# sensorHubRev4.net
KiCad netlist of a schematic drawn in EAGLE
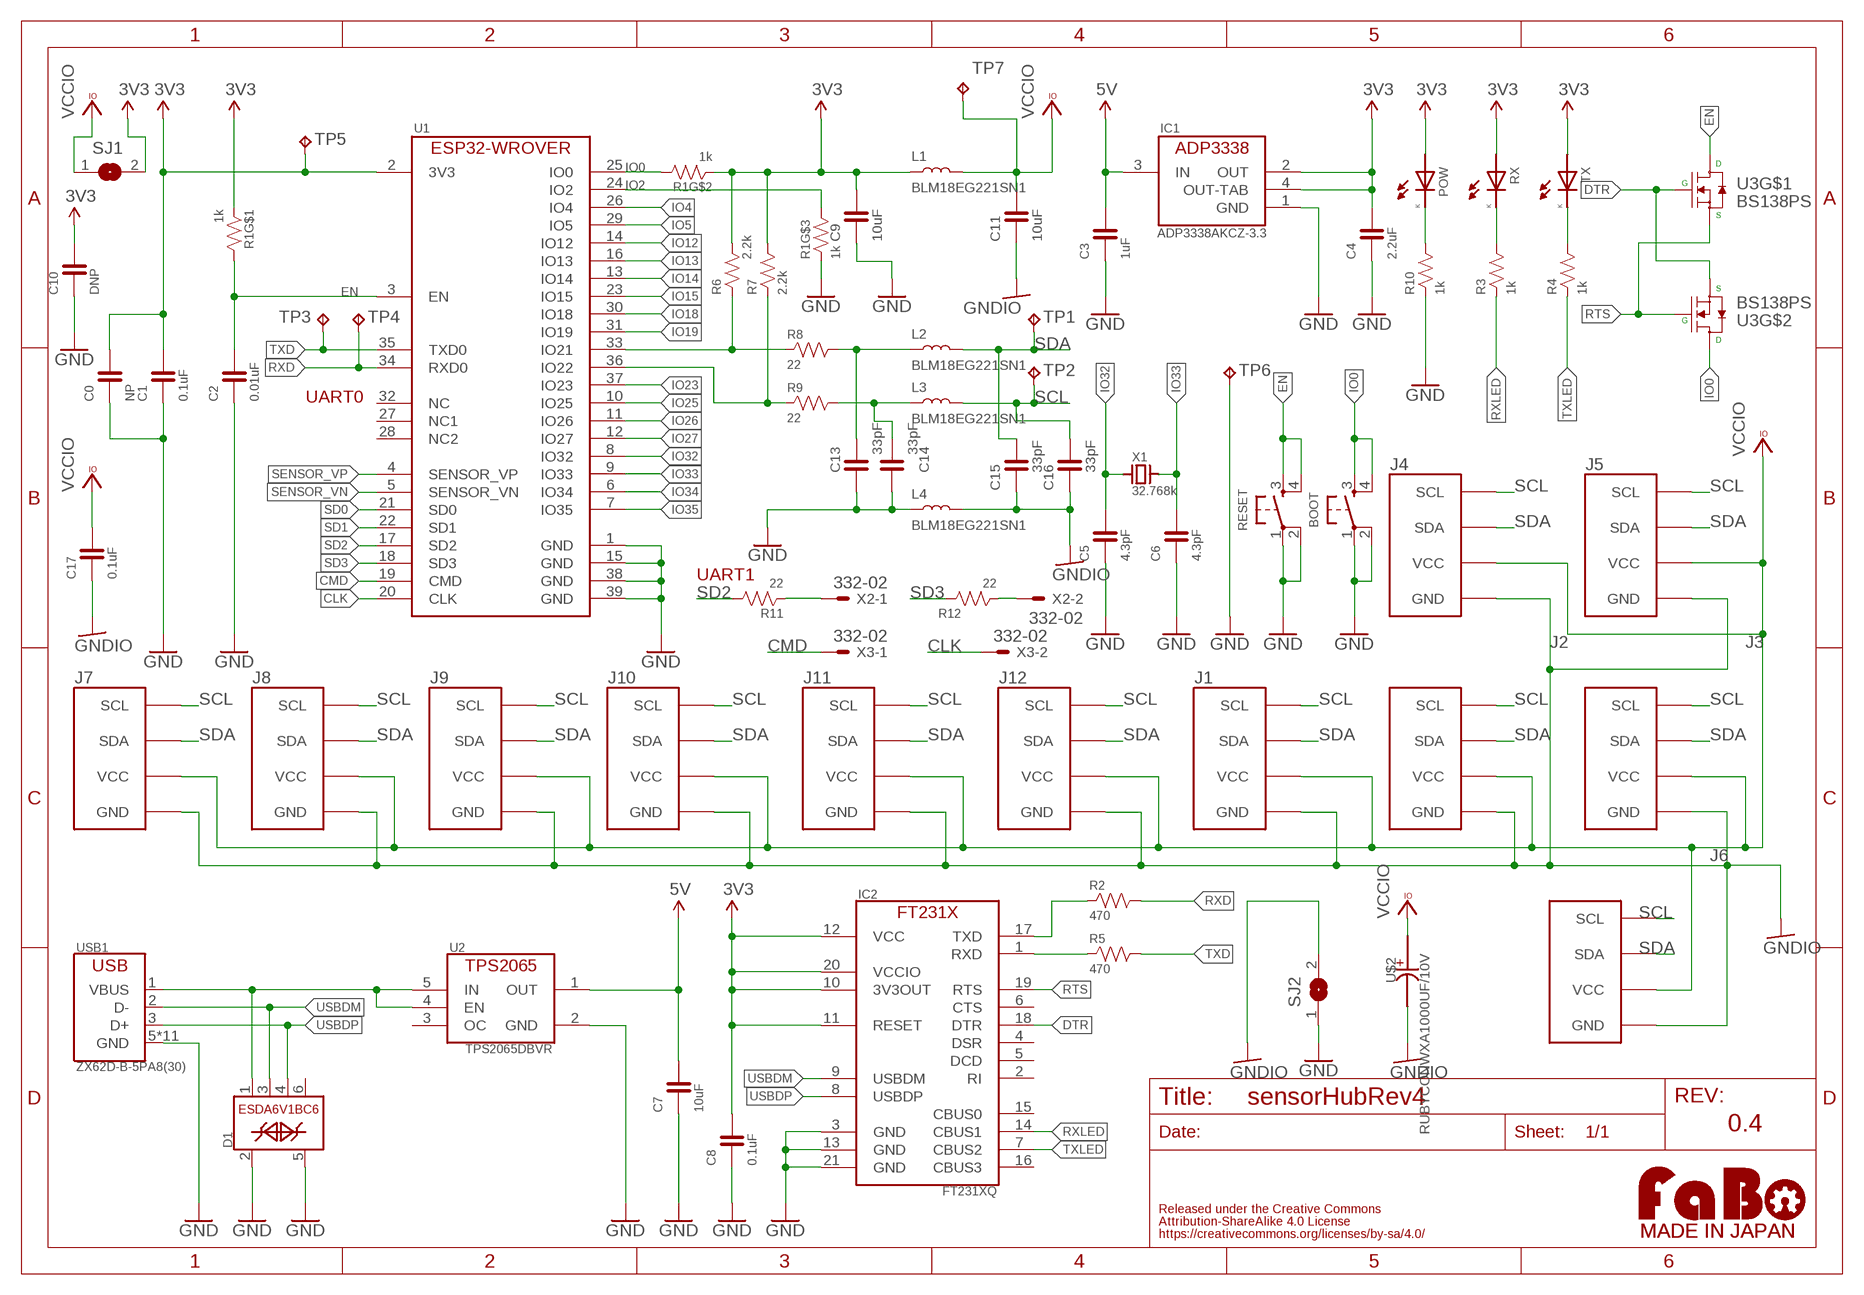
[diagram p0: schematic, sheet 1]

(export (version "E")
  (design (tool "Eeschema 10.0.6"))
  (components
    (comp (ref "BOOT")
      (value "TACTILE-KMR2")
      (footprint "eagle-import:KMR2-TACT")
      (libsource (lib "eagle-import") (part "TACTILE-KMR2"))
    )
    (comp (ref "C0")
      (value "NP")
      (footprint "eagle-import:MULTIPAD0603")
      (libsource (lib "eagle-import") (part "CAPACITOR-M"))
    )
    (comp (ref "C1")
      (value "0.1uF")
      (footprint "eagle-import:EIA0603")
      (libsource (lib "eagle-import") (part "component_CAPACITOR-0603"))
    )
    (comp (ref "C2")
      (value "0.01uF")
      (footprint "eagle-import:EIA0603")
      (libsource (lib "eagle-import") (part "component_CAPACITOR-0603"))
    )
    (comp (ref "C3")
      (value "1uF")
      (footprint "eagle-import:EIA0603")
      (libsource (lib "eagle-import") (part "component_CAPACITOR-0603"))
    )
    (comp (ref "C4")
      (value "2.2uF")
      (footprint "eagle-import:EIA0603")
      (libsource (lib "eagle-import") (part "component_CAPACITOR-0603"))
    )
    (comp (ref "C5")
      (value "4.3pF")
      (footprint "eagle-import:EIA0603")
      (libsource (lib "eagle-import") (part "component_CAPACITOR-0603"))
    )
    (comp (ref "C6")
      (value "4.3pF")
      (footprint "eagle-import:EIA0603")
      (libsource (lib "eagle-import") (part "component_CAPACITOR-0603"))
    )
    (comp (ref "C7")
      (value "10uF")
      (footprint "eagle-import:EIA0603")
      (libsource (lib "eagle-import") (part "component_CAPACITOR-0603"))
    )
    (comp (ref "C8")
      (value "0.1uF")
      (footprint "eagle-import:EIA0603")
      (libsource (lib "eagle-import") (part "component_CAPACITOR-0603"))
    )
    (comp (ref "C9")
      (value "10uF")
      (footprint "eagle-import:0603-NARROW")
      (libsource (lib "eagle-import") (part "CAPACITOR-0603_NARROW"))
    )
    (comp (ref "C10")
      (value "DNP")
      (footprint "eagle-import:EIA0603")
      (libsource (lib "eagle-import") (part "component_CAPACITOR-0603"))
    )
    (comp (ref "C11")
      (value "10uF")
      (footprint "eagle-import:0603-NARROW")
      (libsource (lib "eagle-import") (part "CAPACITOR-0603_NARROW"))
    )
    (comp (ref "C13")
      (value "33pF")
      (footprint "eagle-import:0603-NARROW")
      (libsource (lib "eagle-import") (part "CAPACITOR-0603_NARROW"))
    )
    (comp (ref "C14")
      (value "33pF")
      (footprint "eagle-import:0603-NARROW")
      (libsource (lib "eagle-import") (part "CAPACITOR-0603_NARROW"))
    )
    (comp (ref "C15")
      (value "33pF")
      (footprint "eagle-import:0603-NARROW")
      (libsource (lib "eagle-import") (part "CAPACITOR-0603_NARROW"))
    )
    (comp (ref "C16")
      (value "33pF")
      (footprint "eagle-import:0603-NARROW")
      (libsource (lib "eagle-import") (part "CAPACITOR-0603_NARROW"))
    )
    (comp (ref "C17")
      (value "0.1uF")
      (footprint "eagle-import:EIA0603")
      (libsource (lib "eagle-import") (part "component_CAPACITOR-0603"))
    )
    (comp (ref "D1")
      (value "ESDA6V1BC6")
      (footprint "eagle-import:SOT-23-6L")
      (libsource (lib "eagle-import") (part "ESDA6V1BC6"))
    )
    (comp (ref "IC1")
      (value "ADP3338AKCZ-3.3")
      (footprint "eagle-import:SOT-223-KC3")
      (libsource (lib "eagle-import") (part "ADP3338AKCZ"))
    )
    (comp (ref "IC2")
      (value "FT231XQ")
      (footprint "eagle-import:QFN-20")
      (libsource (lib "eagle-import") (part "FT231XQ"))
    )
    (comp (ref "J1")
      (value "FABO_BRICK_I2C-S04B-PASK-2")
      (footprint "eagle-import:FABO_BRICK_I2C_S04B-PASK-2")
      (libsource (lib "eagle-import") (part "FABO_BRICK_I2C-S04B-PASK-2"))
    )
    (comp (ref "J2")
      (value "FABO_BRICK_I2C-S04B-PASK-2")
      (footprint "eagle-import:FABO_BRICK_I2C_S04B-PASK-2")
      (libsource (lib "eagle-import") (part "FABO_BRICK_I2C-S04B-PASK-2"))
    )
    (comp (ref "J3")
      (value "FABO_BRICK_I2C-S04B-PASK-2")
      (footprint "eagle-import:FABO_BRICK_I2C_S04B-PASK-2")
      (libsource (lib "eagle-import") (part "FABO_BRICK_I2C-S04B-PASK-2"))
    )
    (comp (ref "J4")
      (value "FABO_BRICK_I2C-S04B-PASK-2")
      (footprint "eagle-import:FABO_BRICK_I2C_S04B-PASK-2")
      (libsource (lib "eagle-import") (part "FABO_BRICK_I2C-S04B-PASK-2"))
    )
    (comp (ref "J5")
      (value "FABO_BRICK_I2C-S04B-PASK-2")
      (footprint "eagle-import:FABO_BRICK_I2C_S04B-PASK-2")
      (libsource (lib "eagle-import") (part "FABO_BRICK_I2C-S04B-PASK-2"))
    )
    (comp (ref "J6")
      (value "FABO_BRICK_I2C-S04B-PASK-2")
      (footprint "eagle-import:FABO_BRICK_I2C_S04B-PASK-2")
      (libsource (lib "eagle-import") (part "FABO_BRICK_I2C-S04B-PASK-2"))
    )
    (comp (ref "J7")
      (value "FABO_BRICK_I2C-S04B-PASK-2")
      (footprint "eagle-import:FABO_BRICK_I2C_S04B-PASK-2")
      (libsource (lib "eagle-import") (part "FABO_BRICK_I2C-S04B-PASK-2"))
    )
    (comp (ref "J8")
      (value "FABO_BRICK_I2C-S04B-PASK-2")
      (footprint "eagle-import:FABO_BRICK_I2C_S04B-PASK-2")
      (libsource (lib "eagle-import") (part "FABO_BRICK_I2C-S04B-PASK-2"))
    )
    (comp (ref "J9")
      (value "FABO_BRICK_I2C-S04B-PASK-2")
      (footprint "eagle-import:FABO_BRICK_I2C_S04B-PASK-2")
      (libsource (lib "eagle-import") (part "FABO_BRICK_I2C-S04B-PASK-2"))
    )
    (comp (ref "J10")
      (value "FABO_BRICK_I2C-S04B-PASK-2")
      (footprint "eagle-import:FABO_BRICK_I2C_S04B-PASK-2")
      (libsource (lib "eagle-import") (part "FABO_BRICK_I2C-S04B-PASK-2"))
    )
    (comp (ref "J11")
      (value "FABO_BRICK_I2C-S04B-PASK-2")
      (footprint "eagle-import:FABO_BRICK_I2C_S04B-PASK-2")
      (libsource (lib "eagle-import") (part "FABO_BRICK_I2C-S04B-PASK-2"))
    )
    (comp (ref "J12")
      (value "FABO_BRICK_I2C-S04B-PASK-2")
      (footprint "eagle-import:FABO_BRICK_I2C_S04B-PASK-2")
      (libsource (lib "eagle-import") (part "FABO_BRICK_I2C-S04B-PASK-2"))
    )
    (comp (ref "L1")
      (value "BLM18EG221SN1")
      (footprint "eagle-import:0603")
      (libsource (lib "eagle-import") (part "INDUCTOR-0603"))
    )
    (comp (ref "L2")
      (value "BLM18EG221SN1")
      (footprint "eagle-import:0603")
      (libsource (lib "eagle-import") (part "INDUCTOR-0603"))
    )
    (comp (ref "L3")
      (value "BLM18EG221SN1")
      (footprint "eagle-import:0603")
      (libsource (lib "eagle-import") (part "INDUCTOR-0603"))
    )
    (comp (ref "L4")
      (value "BLM18EG221SN1")
      (footprint "eagle-import:0603")
      (libsource (lib "eagle-import") (part "INDUCTOR-0603"))
    )
    (comp (ref "LOGO1")
      (value "LOGO_FABO-M_BOTTOM")
      (footprint "eagle-import:LOGO_FABO_M_BOTTOM")
      (libsource (lib "eagle-import") (part "LOGO_FABO-M_BOTTOM"))
    )
    (comp (ref "POW")
      (value "LED-0603")
      (footprint "eagle-import:LED_0603")
      (libsource (lib "eagle-import") (part "LED-0603"))
    )
    (comp (ref "R1")
      (value "1k")
      (footprint "eagle-import:EXBV8V")
      (libsource (lib "eagle-import") (part "RESISTOR_ARRAY"))
    )
    (comp (ref "R2")
      (value "470")
      (footprint "eagle-import:EIA0603")
      (libsource (lib "eagle-import") (part "RESISTOR-0603"))
    )
    (comp (ref "R3")
      (value "1k")
      (footprint "eagle-import:EIA0603")
      (libsource (lib "eagle-import") (part "RESISTOR-0603"))
    )
    (comp (ref "R4")
      (value "1k")
      (footprint "eagle-import:EIA0603")
      (libsource (lib "eagle-import") (part "RESISTOR-0603"))
    )
    (comp (ref "R5")
      (value "470")
      (footprint "eagle-import:EIA0603")
      (libsource (lib "eagle-import") (part "RESISTOR-0603"))
    )
    (comp (ref "R6")
      (value "2.2k")
      (footprint "eagle-import:EIA0603")
      (libsource (lib "eagle-import") (part "RESISTOR-0603"))
    )
    (comp (ref "R7")
      (value "2.2k")
      (footprint "eagle-import:EIA0603")
      (libsource (lib "eagle-import") (part "RESISTOR-0603"))
    )
    (comp (ref "R8")
      (value "22")
      (footprint "eagle-import:EIA0603")
      (libsource (lib "eagle-import") (part "RESISTOR-0603"))
    )
    (comp (ref "R9")
      (value "22")
      (footprint "eagle-import:EIA0603")
      (libsource (lib "eagle-import") (part "RESISTOR-0603"))
    )
    (comp (ref "R10")
      (value "1k")
      (footprint "eagle-import:EIA0603")
      (libsource (lib "eagle-import") (part "RESISTOR-0603"))
    )
    (comp (ref "R11")
      (value "22")
      (footprint "eagle-import:EIA0603")
      (libsource (lib "eagle-import") (part "RESISTOR-0603"))
    )
    (comp (ref "R12")
      (value "22")
      (footprint "eagle-import:EIA0603")
      (libsource (lib "eagle-import") (part "RESISTOR-0603"))
    )
    (comp (ref "RESET")
      (value "TACTILE-KMR2")
      (footprint "eagle-import:KMR2-TACT")
      (libsource (lib "eagle-import") (part "TACTILE-KMR2"))
    )
    (comp (ref "RX")
      (value "LED-0603")
      (footprint "eagle-import:LED_0603")
      (libsource (lib "eagle-import") (part "LED-0603"))
    )
    (comp (ref "SJ1") (value "SJ") (footprint "eagle-import:SJ") (libsource (lib "eagle-import") (part "SJ")))
    (comp (ref "SJ2") (value "SJ") (footprint "eagle-import:SJ") (libsource (lib "eagle-import") (part "SJ")))
    (comp (ref "TP1")
      (value "TPB1,27")
      (footprint "eagle-import:B1,27")
      (libsource (lib "eagle-import") (part "TPB1,27"))
    )
    (comp (ref "TP2")
      (value "TPB1,27")
      (footprint "eagle-import:B1,27")
      (libsource (lib "eagle-import") (part "TPB1,27"))
    )
    (comp (ref "TP3")
      (value "TPB1,27")
      (footprint "eagle-import:B1,27")
      (libsource (lib "eagle-import") (part "TPB1,27"))
    )
    (comp (ref "TP4")
      (value "TPB1,27")
      (footprint "eagle-import:B1,27")
      (libsource (lib "eagle-import") (part "TPB1,27"))
    )
    (comp (ref "TP5")
      (value "TPB1,27")
      (footprint "eagle-import:B1,27")
      (libsource (lib "eagle-import") (part "TPB1,27"))
    )
    (comp (ref "TP6")
      (value "TPB1,27")
      (footprint "eagle-import:B1,27")
      (libsource (lib "eagle-import") (part "TPB1,27"))
    )
    (comp (ref "TP7")
      (value "TPB1,27")
      (footprint "eagle-import:B1,27")
      (libsource (lib "eagle-import") (part "TPB1,27"))
    )
    (comp (ref "TX")
      (value "LED-0603")
      (footprint "eagle-import:LED_0603")
      (libsource (lib "eagle-import") (part "LED-0603"))
    )
    (comp (ref "U$2")
      (value "RUBYCONWXA1000UF/10V")
      (footprint "eagle-import:ALUMINUM10_9")
      (libsource (lib "eagle-import") (part "RUBYCONWXA1000UF/10V"))
    )
    (comp (ref "U1")
      (value "ESP32-WROVER-B")
      (footprint "eagle-import:ESP32-WROVER-B")
      (libsource (lib "eagle-import") (part "ESP32-WROVER-B"))
    )
    (comp (ref "U2")
      (value "TPS2065DBVR")
      (footprint "eagle-import:SOT-23-5")
      (libsource (lib "eagle-import") (part "TPS2065DBV"))
    )
    (comp (ref "U3")
      (value "BS138PS")
      (footprint "eagle-import:SOT-363")
      (libsource (lib "eagle-import") (part "BS138PS"))
    )
    (comp (ref "USB1")
      (value "ZX62D-B-5PA8(30)")
      (footprint "eagle-import:ZX62D-B-5PA8")
      (libsource (lib "eagle-import") (part "USB-ZX62D"))
    )
    (comp (ref "X1")
      (value "32.768k")
      (footprint "eagle-import:ABS07")
      (libsource (lib "eagle-import") (part "CRYSTAL-ABS07"))
    )
    (comp (ref "X2")
      (value "332-02")
      (footprint "eagle-import:332-02")
      (libsource (lib "eagle-import") (part "332-02"))
    )
    (comp (ref "X3")
      (value "332-02")
      (footprint "eagle-import:332-02")
      (libsource (lib "eagle-import") (part "332-02"))
    )
  )
  (nets
    (net (code "1") (name "/IO2") (class "Default")
      (node (ref "R1") (pin "6") (pinfunction "2_6") (pintype "bidirectional"))
      (node (ref "U1") (pin "24") (pinfunction "IO2_24") (pintype "bidirectional"))
    )
    (net (code "2") (name "/SCL") (class "Default")
      (node (ref "C16") (pin "2") (pinfunction "2_2") (pintype "passive"))
      (node (ref "J1") (pin "SCL") (pinfunction "SCL_SCL") (pintype "bidirectional"))
      (node (ref "J10") (pin "SCL") (pinfunction "SCL_SCL") (pintype "bidirectional"))
      (node (ref "J11") (pin "SCL") (pinfunction "SCL_SCL") (pintype "bidirectional"))
      (node (ref "J12") (pin "SCL") (pinfunction "SCL_SCL") (pintype "bidirectional"))
      (node (ref "J2") (pin "SCL") (pinfunction "SCL_SCL") (pintype "bidirectional"))
      (node (ref "J3") (pin "SCL") (pinfunction "SCL_SCL") (pintype "bidirectional"))
      (node (ref "J4") (pin "SCL") (pinfunction "SCL_SCL") (pintype "bidirectional"))
      (node (ref "J5") (pin "SCL") (pinfunction "SCL_SCL") (pintype "bidirectional"))
      (node (ref "J6") (pin "SCL") (pinfunction "SCL_SCL") (pintype "bidirectional"))
      (node (ref "J7") (pin "SCL") (pinfunction "SCL_SCL") (pintype "bidirectional"))
      (node (ref "J8") (pin "SCL") (pinfunction "SCL_SCL") (pintype "bidirectional"))
      (node (ref "J9") (pin "SCL") (pinfunction "SCL_SCL") (pintype "bidirectional"))
      (node (ref "L3") (pin "2") (pinfunction "2_2") (pintype "bidirectional"))
      (node (ref "TP2") (pin "TP") (pinfunction "TP_TP") (pintype "input"))
    )
    (net (code "3") (name "/SDA") (class "Default")
      (node (ref "C15") (pin "2") (pinfunction "2_2") (pintype "passive"))
      (node (ref "J1") (pin "SDA") (pinfunction "SDA_SDA") (pintype "bidirectional"))
      (node (ref "J10") (pin "SDA") (pinfunction "SDA_SDA") (pintype "bidirectional"))
      (node (ref "J11") (pin "SDA") (pinfunction "SDA_SDA") (pintype "bidirectional"))
      (node (ref "J12") (pin "SDA") (pinfunction "SDA_SDA") (pintype "bidirectional"))
      (node (ref "J2") (pin "SDA") (pinfunction "SDA_SDA") (pintype "bidirectional"))
      (node (ref "J3") (pin "SDA") (pinfunction "SDA_SDA") (pintype "bidirectional"))
      (node (ref "J4") (pin "SDA") (pinfunction "SDA_SDA") (pintype "bidirectional"))
      (node (ref "J5") (pin "SDA") (pinfunction "SDA_SDA") (pintype "bidirectional"))
      (node (ref "J6") (pin "SDA") (pinfunction "SDA_SDA") (pintype "bidirectional"))
      (node (ref "J7") (pin "SDA") (pinfunction "SDA_SDA") (pintype "bidirectional"))
      (node (ref "J8") (pin "SDA") (pinfunction "SDA_SDA") (pintype "bidirectional"))
      (node (ref "J9") (pin "SDA") (pinfunction "SDA_SDA") (pintype "bidirectional"))
      (node (ref "L2") (pin "2") (pinfunction "2_2") (pintype "bidirectional"))
      (node (ref "TP1") (pin "TP") (pinfunction "TP_TP") (pintype "input"))
    )
    (net (code "4") (name "3V3") (class "Default")
      (node (ref "C0") (pin "2") (pinfunction "2_2") (pintype "passive"))
      (node (ref "C1") (pin "2") (pinfunction "2_2") (pintype "passive"))
      (node (ref "C10") (pin "2") (pinfunction "2_2") (pintype "passive"))
      (node (ref "C4") (pin "2") (pinfunction "2_2") (pintype "passive"))
      (node (ref "C8") (pin "2") (pinfunction "2_2") (pintype "passive"))
      (node (ref "C9") (pin "2") (pinfunction "2_2") (pintype "passive"))
      (node (ref "IC1") (pin "2") (pinfunction "OUT_2") (pintype "bidirectional"))
      (node (ref "IC1") (pin "4") (pinfunction "OUT-TAB_4") (pintype "bidirectional"))
      (node (ref "IC2") (pin "10") (pinfunction "3V3OUT_10") (pintype "bidirectional"))
      (node (ref "IC2") (pin "11") (pinfunction "RESET_11") (pintype "bidirectional"))
      (node (ref "IC2") (pin "12") (pinfunction "VCC_12") (pintype "bidirectional"))
      (node (ref "IC2") (pin "20") (pinfunction "VCCIO_20") (pintype "bidirectional"))
      (node (ref "L1") (pin "1") (pinfunction "1_1") (pintype "bidirectional"))
      (node (ref "POW") (pin "A") (pinfunction "ANODE_A") (pintype "passive"))
      (node (ref "R1") (pin "1") (pinfunction "1_1") (pintype "bidirectional"))
      (node (ref "R1") (pin "2") (pinfunction "1_2") (pintype "bidirectional"))
      (node (ref "R6") (pin "2") (pinfunction "2_2") (pintype "bidirectional"))
      (node (ref "R7") (pin "2") (pinfunction "2_2") (pintype "bidirectional"))
      (node (ref "RX") (pin "A") (pinfunction "ANODE_A") (pintype "passive"))
      (node (ref "SJ1") (pin "2") (pinfunction "2_2") (pintype "passive"))
      (node (ref "TP5") (pin "TP") (pinfunction "TP_TP") (pintype "input"))
      (node (ref "TX") (pin "A") (pinfunction "ANODE_A") (pintype "passive"))
      (node (ref "U1") (pin "2") (pinfunction "3V3_2") (pintype "bidirectional"))
    )
    (net (code "5") (name "5V") (class "Default")
      (node (ref "C3") (pin "2") (pinfunction "2_2") (pintype "passive"))
      (node (ref "C7") (pin "2") (pinfunction "2_2") (pintype "passive"))
      (node (ref "IC1") (pin "3") (pinfunction "IN_3") (pintype "bidirectional"))
      (node (ref "U2") (pin "1") (pinfunction "OUT_1") (pintype "bidirectional"))
    )
    (net (code "6") (name "CLK") (class "Default")
      (node (ref "U1") (pin "20") (pinfunction "CLK_20") (pintype "bidirectional"))
      (node (ref "X3") (pin "2") (pinfunction "S_2") (pintype "passive"))
    )
    (net (code "7") (name "CMD") (class "Default")
      (node (ref "U1") (pin "19") (pinfunction "CMD_19") (pintype "bidirectional"))
      (node (ref "X3") (pin "1") (pinfunction "S_1") (pintype "passive"))
    )
    (net (code "8") (name "DTR") (class "Default")
      (node (ref "IC2") (pin "18") (pinfunction "DTR_18") (pintype "bidirectional"))
      (node (ref "U3") (pin "2") (pinfunction "G_2") (pintype "passive"))
      (node (ref "U3") (pin "4") (pinfunction "S_4") (pintype "passive"))
    )
    (net (code "9") (name "EN") (class "Default")
      (node (ref "C2") (pin "2") (pinfunction "2_2") (pintype "passive"))
      (node (ref "R1") (pin "8") (pinfunction "2_8") (pintype "bidirectional"))
      (node (ref "RESET") (pin "3") (pinfunction "3_3") (pintype "passive"))
      (node (ref "RESET") (pin "4") (pinfunction "4_4") (pintype "passive"))
      (node (ref "U1") (pin "3") (pinfunction "EN_3") (pintype "bidirectional"))
      (node (ref "U3") (pin "6") (pinfunction "D_6") (pintype "passive"))
    )
    (net (code "10") (name "GND") (class "Default")
      (node (ref "BOOT") (pin "1") (pinfunction "1_1") (pintype "passive"))
      (node (ref "BOOT") (pin "2") (pinfunction "2_2") (pintype "passive"))
      (node (ref "C0") (pin "1") (pinfunction "1_1") (pintype "passive"))
      (node (ref "C1") (pin "1") (pinfunction "1_1") (pintype "passive"))
      (node (ref "C10") (pin "1") (pinfunction "1_1") (pintype "passive"))
      (node (ref "C13") (pin "1") (pinfunction "1_1") (pintype "passive"))
      (node (ref "C14") (pin "1") (pinfunction "1_1") (pintype "passive"))
      (node (ref "C2") (pin "1") (pinfunction "1_1") (pintype "passive"))
      (node (ref "C3") (pin "1") (pinfunction "1_1") (pintype "passive"))
      (node (ref "C4") (pin "1") (pinfunction "1_1") (pintype "passive"))
      (node (ref "C5") (pin "1") (pinfunction "1_1") (pintype "passive"))
      (node (ref "C6") (pin "1") (pinfunction "1_1") (pintype "passive"))
      (node (ref "C7") (pin "1") (pinfunction "1_1") (pintype "passive"))
      (node (ref "C8") (pin "1") (pinfunction "1_1") (pintype "passive"))
      (node (ref "C9") (pin "1") (pinfunction "1_1") (pintype "passive"))
      (node (ref "D1") (pin "2") (pinfunction "2_2") (pintype "bidirectional"))
      (node (ref "D1") (pin "5") (pinfunction "5_5") (pintype "bidirectional"))
      (node (ref "IC1") (pin "1") (pinfunction "GND_1") (pintype "bidirectional"))
      (node (ref "IC2") (pin "13") (pinfunction "GND_13") (pintype "bidirectional"))
      (node (ref "IC2") (pin "21") (pinfunction "GND_21") (pintype "bidirectional"))
      (node (ref "IC2") (pin "3") (pinfunction "GND_3") (pintype "bidirectional"))
      (node (ref "L4") (pin "1") (pinfunction "1_1") (pintype "bidirectional"))
      (node (ref "R1") (pin "3") (pinfunction "1_3") (pintype "bidirectional"))
      (node (ref "R10") (pin "1") (pinfunction "1_1") (pintype "bidirectional"))
      (node (ref "RESET") (pin "1") (pinfunction "1_1") (pintype "passive"))
      (node (ref "RESET") (pin "2") (pinfunction "2_2") (pintype "passive"))
      (node (ref "SJ2") (pin "1") (pinfunction "1_1") (pintype "passive"))
      (node (ref "TP6") (pin "TP") (pinfunction "TP_TP") (pintype "input"))
      (node (ref "U1") (pin "1") (pinfunction "GND_1") (pintype "bidirectional"))
      (node (ref "U1") (pin "15") (pinfunction "GND_15") (pintype "bidirectional"))
      (node (ref "U1") (pin "38") (pinfunction "GND_38") (pintype "bidirectional"))
      (node (ref "U1") (pin "39") (pinfunction "GND_39") (pintype "bidirectional"))
      (node (ref "U2") (pin "2") (pinfunction "GND_2") (pintype "bidirectional"))
      (node (ref "USB1") (pin "5") (pinfunction "GND_5") (pintype "bidirectional"))
      (node (ref "USB1") (pin "B1") (pinfunction "GND_B1") (pintype "bidirectional"))
      (node (ref "USB1") (pin "B2") (pinfunction "GND_B2") (pintype "bidirectional"))
      (node (ref "USB1") (pin "B3") (pinfunction "GND_B3") (pintype "bidirectional"))
      (node (ref "USB1") (pin "B4") (pinfunction "GND_B4") (pintype "bidirectional"))
      (node (ref "USB1") (pin "T1") (pinfunction "GND_T1") (pintype "bidirectional"))
      (node (ref "USB1") (pin "T2") (pinfunction "GND_T2") (pintype "bidirectional"))
      (node (ref "USB1") (pin "T3") (pinfunction "GND_T3") (pintype "bidirectional"))
      (node (ref "USB1") (pin "T4") (pinfunction "GND_T4") (pintype "bidirectional"))
      (node (ref "USB1") (pin "T5") (pinfunction "GND_T5") (pintype "bidirectional"))
      (node (ref "USB1") (pin "T6") (pinfunction "GND_T6") (pintype "bidirectional"))
    )
    (net (code "11") (name "GNDIO") (class "Default")
      (node (ref "C11") (pin "1") (pinfunction "1_1") (pintype "passive"))
      (node (ref "C15") (pin "1") (pinfunction "1_1") (pintype "passive"))
      (node (ref "C16") (pin "1") (pinfunction "1_1") (pintype "passive"))
      (node (ref "C17") (pin "1") (pinfunction "1_1") (pintype "passive"))
      (node (ref "J1") (pin "GND") (pinfunction "GND_GND") (pintype "bidirectional"))
      (node (ref "J10") (pin "GND") (pinfunction "GND_GND") (pintype "bidirectional"))
      (node (ref "J11") (pin "GND") (pinfunction "GND_GND") (pintype "bidirectional"))
      (node (ref "J12") (pin "GND") (pinfunction "GND_GND") (pintype "bidirectional"))
      (node (ref "J2") (pin "GND") (pinfunction "GND_GND") (pintype "bidirectional"))
      (node (ref "J3") (pin "GND") (pinfunction "GND_GND") (pintype "bidirectional"))
      (node (ref "J4") (pin "GND") (pinfunction "GND_GND") (pintype "bidirectional"))
      (node (ref "J5") (pin "GND") (pinfunction "GND_GND") (pintype "bidirectional"))
      (node (ref "J6") (pin "GND") (pinfunction "GND_GND") (pintype "bidirectional"))
      (node (ref "J7") (pin "GND") (pinfunction "GND_GND") (pintype "bidirectional"))
      (node (ref "J8") (pin "GND") (pinfunction "GND_GND") (pintype "bidirectional"))
      (node (ref "J9") (pin "GND") (pinfunction "GND_GND") (pintype "bidirectional"))
      (node (ref "L4") (pin "2") (pinfunction "2_2") (pintype "bidirectional"))
      (node (ref "SJ2") (pin "2") (pinfunction "2_2") (pintype "passive"))
      (node (ref "U$2") (pin "MINUS") (pinfunction "-_MINUS") (pintype "passive"))
    )
    (net (code "12") (name "IO0") (class "Default")
      (node (ref "BOOT") (pin "3") (pinfunction "3_3") (pintype "passive"))
      (node (ref "BOOT") (pin "4") (pinfunction "4_4") (pintype "passive"))
      (node (ref "R1") (pin "7") (pinfunction "2_7") (pintype "bidirectional"))
      (node (ref "U1") (pin "25") (pinfunction "IO0_25") (pintype "bidirectional"))
      (node (ref "U3") (pin "3") (pinfunction "D_3") (pintype "passive"))
    )
    (net (code "13") (name "IO4") (class "Default")
      (node (ref "U1") (pin "26") (pinfunction "IO4_26") (pintype "bidirectional"))
    )
    (net (code "14") (name "IO5") (class "Default")
      (node (ref "U1") (pin "29") (pinfunction "IO5_29") (pintype "bidirectional"))
    )
    (net (code "15") (name "IO12") (class "Default")
      (node (ref "U1") (pin "14") (pinfunction "IO12_14") (pintype "bidirectional"))
    )
    (net (code "16") (name "IO13") (class "Default")
      (node (ref "U1") (pin "16") (pinfunction "IO13_16") (pintype "bidirectional"))
    )
    (net (code "17") (name "IO14") (class "Default")
      (node (ref "U1") (pin "13") (pinfunction "IO14_13") (pintype "bidirectional"))
    )
    (net (code "18") (name "IO15") (class "Default")
      (node (ref "U1") (pin "23") (pinfunction "IO15_23") (pintype "bidirectional"))
    )
    (net (code "19") (name "IO18") (class "Default")
      (node (ref "U1") (pin "30") (pinfunction "IO18_30") (pintype "bidirectional"))
    )
    (net (code "20") (name "IO19") (class "Default")
      (node (ref "U1") (pin "31") (pinfunction "IO19_31") (pintype "bidirectional"))
    )
    (net (code "21") (name "IO23") (class "Default")
      (node (ref "U1") (pin "37") (pinfunction "IO23_37") (pintype "bidirectional"))
    )
    (net (code "22") (name "IO25") (class "Default")
      (node (ref "U1") (pin "10") (pinfunction "IO25_10") (pintype "bidirectional"))
    )
    (net (code "23") (name "IO26") (class "Default")
      (node (ref "U1") (pin "11") (pinfunction "IO26_11") (pintype "bidirectional"))
    )
    (net (code "24") (name "IO27") (class "Default")
      (node (ref "U1") (pin "12") (pinfunction "IO27_12") (pintype "bidirectional"))
    )
    (net (code "25") (name "IO32") (class "Default")
      (node (ref "C5") (pin "2") (pinfunction "2_2") (pintype "passive"))
      (node (ref "U1") (pin "8") (pinfunction "IO32_8") (pintype "bidirectional"))
      (node (ref "X1") (pin "1") (pinfunction "P$1_1") (pintype "bidirectional"))
    )
    (net (code "26") (name "IO33") (class "Default")
      (node (ref "C6") (pin "2") (pinfunction "2_2") (pintype "passive"))
      (node (ref "U1") (pin "9") (pinfunction "IO33_9") (pintype "bidirectional"))
      (node (ref "X1") (pin "2") (pinfunction "P$2_2") (pintype "bidirectional"))
    )
    (net (code "27") (name "IO34") (class "Default")
      (node (ref "U1") (pin "6") (pinfunction "IO34_6") (pintype "bidirectional"))
    )
    (net (code "28") (name "IO35") (class "Default")
      (node (ref "U1") (pin "7") (pinfunction "IO35_7") (pintype "bidirectional"))
    )
    (net (code "29") (name "Net-(C13-Pad2)") (class "Default")
      (node (ref "C13") (pin "2") (pinfunction "2_2") (pintype "passive"))
      (node (ref "L2") (pin "1") (pinfunction "1_1") (pintype "bidirectional"))
      (node (ref "R8") (pin "2") (pinfunction "2_2") (pintype "bidirectional"))
    )
    (net (code "30") (name "Net-(C14-Pad2)") (class "Default")
      (node (ref "C14") (pin "2") (pinfunction "2_2") (pintype "passive"))
      (node (ref "L3") (pin "1") (pinfunction "1_1") (pintype "bidirectional"))
      (node (ref "R9") (pin "2") (pinfunction "2_2") (pintype "bidirectional"))
    )
    (net (code "31") (name "Net-(IC2-RXD)") (class "Default")
      (node (ref "IC2") (pin "1") (pinfunction "RXD_1") (pintype "bidirectional"))
      (node (ref "R5") (pin "1") (pinfunction "1_1") (pintype "bidirectional"))
    )
    (net (code "32") (name "Net-(IC2-TXD)") (class "Default")
      (node (ref "IC2") (pin "17") (pinfunction "TXD_17") (pintype "bidirectional"))
      (node (ref "R2") (pin "1") (pinfunction "1_1") (pintype "bidirectional"))
    )
    (net (code "33") (name "Net-(POW-CATHODE)") (class "Default")
      (node (ref "POW") (pin "K") (pinfunction "CATHODE_K") (pintype "passive"))
      (node (ref "R10") (pin "2") (pinfunction "2_2") (pintype "bidirectional"))
    )
    (net (code "34") (name "Net-(RX-CATHODE)") (class "Default")
      (node (ref "R3") (pin "2") (pinfunction "2_2") (pintype "bidirectional"))
      (node (ref "RX") (pin "K") (pinfunction "CATHODE_K") (pintype "passive"))
    )
    (net (code "35") (name "Net-(TX-CATHODE)") (class "Default")
      (node (ref "R4") (pin "2") (pinfunction "2_2") (pintype "bidirectional"))
      (node (ref "TX") (pin "K") (pinfunction "CATHODE_K") (pintype "passive"))
    )
    (net (code "36") (name "Net-(U1-IO21)") (class "Default")
      (node (ref "R6") (pin "1") (pinfunction "1_1") (pintype "bidirectional"))
      (node (ref "R8") (pin "1") (pinfunction "1_1") (pintype "bidirectional"))
      (node (ref "U1") (pin "33") (pinfunction "IO21_33") (pintype "bidirectional"))
    )
    (net (code "37") (name "Net-(U1-IO22)") (class "Default")
      (node (ref "R7") (pin "1") (pinfunction "1_1") (pintype "bidirectional"))
      (node (ref "R9") (pin "1") (pinfunction "1_1") (pintype "bidirectional"))
      (node (ref "U1") (pin "36") (pinfunction "IO22_36") (pintype "bidirectional"))
    )
    (net (code "38") (name "Net-(U2-EN)") (class "Default")
      (node (ref "D1") (pin "1") (pinfunction "1_1") (pintype "bidirectional"))
      (node (ref "U2") (pin "4") (pinfunction "EN_4") (pintype "bidirectional"))
      (node (ref "U2") (pin "5") (pinfunction "IN_5") (pintype "bidirectional"))
      (node (ref "USB1") (pin "1") (pinfunction "VBUS_1") (pintype "bidirectional"))
    )
    (net (code "39") (name "Net-(X2A-S)") (class "Default")
      (node (ref "R11") (pin "1") (pinfunction "1_1") (pintype "bidirectional"))
      (node (ref "X2") (pin "1") (pinfunction "S_1") (pintype "passive"))
    )
    (net (code "40") (name "Net-(X2B-S)") (class "Default")
      (node (ref "R12") (pin "1") (pinfunction "1_1") (pintype "bidirectional"))
      (node (ref "X2") (pin "2") (pinfunction "S_2") (pintype "passive"))
    )
    (net (code "41") (name "RTS") (class "Default")
      (node (ref "IC2") (pin "19") (pinfunction "RTS_19") (pintype "bidirectional"))
      (node (ref "U3") (pin "1") (pinfunction "S_1") (pintype "passive"))
      (node (ref "U3") (pin "5") (pinfunction "G_5") (pintype "passive"))
    )
    (net (code "42") (name "RXD") (class "Default")
      (node (ref "R2") (pin "2") (pinfunction "2_2") (pintype "bidirectional"))
      (node (ref "TP4") (pin "TP") (pinfunction "TP_TP") (pintype "input"))
      (node (ref "U1") (pin "34") (pinfunction "RXD0_34") (pintype "bidirectional"))
    )
    (net (code "43") (name "RXLED") (class "Default")
      (node (ref "IC2") (pin "14") (pinfunction "CBUS1_14") (pintype "bidirectional"))
      (node (ref "R3") (pin "1") (pinfunction "1_1") (pintype "bidirectional"))
    )
    (net (code "44") (name "SD0") (class "Default")
      (node (ref "U1") (pin "21") (pinfunction "SD0_21") (pintype "bidirectional"))
    )
    (net (code "45") (name "SD1") (class "Default")
      (node (ref "U1") (pin "22") (pinfunction "SD1_22") (pintype "bidirectional"))
    )
    (net (code "46") (name "SD2") (class "Default")
      (node (ref "R11") (pin "2") (pinfunction "2_2") (pintype "bidirectional"))
      (node (ref "U1") (pin "17") (pinfunction "SD2_17") (pintype "bidirectional"))
    )
    (net (code "47") (name "SD3") (class "Default")
      (node (ref "R12") (pin "2") (pinfunction "2_2") (pintype "bidirectional"))
      (node (ref "U1") (pin "18") (pinfunction "SD3_18") (pintype "bidirectional"))
    )
    (net (code "48") (name "SENSOR_VN") (class "Default")
      (node (ref "U1") (pin "5") (pinfunction "SENSOR_VN_5") (pintype "bidirectional"))
    )
    (net (code "49") (name "SENSOR_VP") (class "Default")
      (node (ref "U1") (pin "4") (pinfunction "SENSOR_VP_4") (pintype "bidirectional"))
    )
    (net (code "50") (name "TXD") (class "Default")
      (node (ref "R5") (pin "2") (pinfunction "2_2") (pintype "bidirectional"))
      (node (ref "TP3") (pin "TP") (pinfunction "TP_TP") (pintype "input"))
      (node (ref "U1") (pin "35") (pinfunction "TXD0_35") (pintype "bidirectional"))
    )
    (net (code "51") (name "TXLED") (class "Default")
      (node (ref "IC2") (pin "7") (pinfunction "CBUS2_7") (pintype "bidirectional"))
      (node (ref "R4") (pin "1") (pinfunction "1_1") (pintype "bidirectional"))
    )
    (net (code "52") (name "USBDM") (class "Default")
      (node (ref "D1") (pin "3") (pinfunction "3_3") (pintype "bidirectional"))
      (node (ref "IC2") (pin "9") (pinfunction "USBDM_9") (pintype "bidirectional"))
      (node (ref "USB1") (pin "2") (pinfunction "D-_2") (pintype "bidirectional"))
    )
    (net (code "53") (name "USBDP") (class "Default")
      (node (ref "D1") (pin "4") (pinfunction "4_4") (pintype "bidirectional"))
      (node (ref "IC2") (pin "8") (pinfunction "USBDP_8") (pintype "bidirectional"))
      (node (ref "USB1") (pin "3") (pinfunction "D+_3") (pintype "bidirectional"))
    )
    (net (code "54") (name "VCCIO") (class "Default")
      (node (ref "C11") (pin "2") (pinfunction "2_2") (pintype "passive"))
      (node (ref "C17") (pin "2") (pinfunction "2_2") (pintype "passive"))
      (node (ref "J1") (pin "VCC") (pinfunction "VCC_VCC") (pintype "bidirectional"))
      (node (ref "J10") (pin "VCC") (pinfunction "VCC_VCC") (pintype "bidirectional"))
      (node (ref "J11") (pin "VCC") (pinfunction "VCC_VCC") (pintype "bidirectional"))
      (node (ref "J12") (pin "VCC") (pinfunction "VCC_VCC") (pintype "bidirectional"))
      (node (ref "J2") (pin "VCC") (pinfunction "VCC_VCC") (pintype "bidirectional"))
      (node (ref "J3") (pin "VCC") (pinfunction "VCC_VCC") (pintype "bidirectional"))
      (node (ref "J4") (pin "VCC") (pinfunction "VCC_VCC") (pintype "bidirectional"))
      (node (ref "J5") (pin "VCC") (pinfunction "VCC_VCC") (pintype "bidirectional"))
      (node (ref "J6") (pin "VCC") (pinfunction "VCC_VCC") (pintype "bidirectional"))
      (node (ref "J7") (pin "VCC") (pinfunction "VCC_VCC") (pintype "bidirectional"))
      (node (ref "J8") (pin "VCC") (pinfunction "VCC_VCC") (pintype "bidirectional"))
      (node (ref "J9") (pin "VCC") (pinfunction "VCC_VCC") (pintype "bidirectional"))
      (node (ref "L1") (pin "2") (pinfunction "2_2") (pintype "bidirectional"))
      (node (ref "SJ1") (pin "1") (pinfunction "1_1") (pintype "passive"))
      (node (ref "TP7") (pin "TP") (pinfunction "TP_TP") (pintype "input"))
      (node (ref "U$2") (pin "PLUS") (pinfunction "+_PLUS") (pintype "passive"))
    )
    (net (code "55") (name "unconnected-(D1-Pad6)") (class "Default")
      (node (ref "D1") (pin "6") (pinfunction "6_6") (pintype "bidirectional"))
    )
    (net (code "56") (name "unconnected-(IC2-CBUS0-Pad15)") (class "Default")
      (node (ref "IC2") (pin "15") (pinfunction "CBUS0_15") (pintype "bidirectional"))
    )
    (net (code "57") (name "unconnected-(IC2-CBUS3-Pad16)") (class "Default")
      (node (ref "IC2") (pin "16") (pinfunction "CBUS3_16") (pintype "bidirectional"))
    )
    (net (code "58") (name "unconnected-(IC2-CTS-Pad6)") (class "Default")
      (node (ref "IC2") (pin "6") (pinfunction "CTS_6") (pintype "bidirectional"))
    )
    (net (code "59") (name "unconnected-(IC2-DCD-Pad5)") (class "Default")
      (node (ref "IC2") (pin "5") (pinfunction "DCD_5") (pintype "bidirectional"))
    )
    (net (code "60") (name "unconnected-(IC2-DSR-Pad4)") (class "Default")
      (node (ref "IC2") (pin "4") (pinfunction "DSR_4") (pintype "bidirectional"))
    )
    (net (code "61") (name "unconnected-(IC2-RI-Pad2)") (class "Default")
      (node (ref "IC2") (pin "2") (pinfunction "RI_2") (pintype "bidirectional"))
    )
    (net (code "62") (name "unconnected-(U1-NC-Pad32)") (class "Default")
      (node (ref "U1") (pin "32") (pinfunction "NC_32") (pintype "bidirectional"))
    )
    (net (code "63") (name "unconnected-(U1-NC1-Pad27)") (class "Default")
      (node (ref "U1") (pin "27") (pinfunction "NC1_27") (pintype "bidirectional"))
    )
    (net (code "64") (name "unconnected-(U1-NC2-Pad28)") (class "Default")
      (node (ref "U1") (pin "28") (pinfunction "NC2_28") (pintype "bidirectional"))
    )
    (net (code "65") (name "unconnected-(U2-OC-Pad3)") (class "Default")
      (node (ref "U2") (pin "3") (pinfunction "OC_3") (pintype "bidirectional"))
    )
  )
)
